# ESP32.net
KiCad netlist of a schematic drawn in Altium Designer
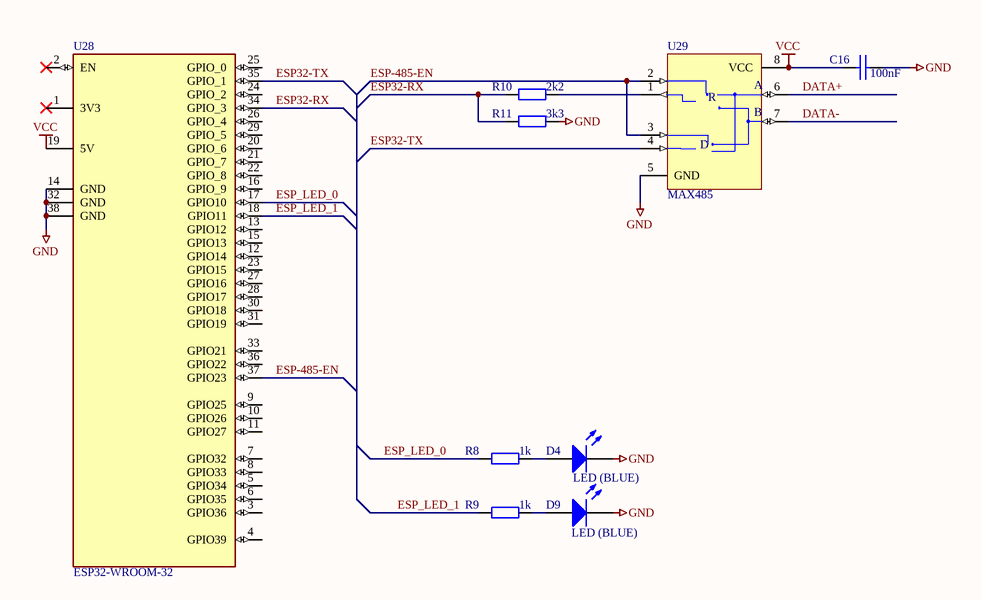
[diagram p0: ESP32.SchDoc]

(export (version "E")
  (design (tool "Eeschema 10.0.6"))
  (components
    (comp (ref "C16")
      (value "100nF")
      (footprint "CAPACITOR 0805")
      (description "CAPACITOR SMD 0603")
      (fields (field (name "MOUSER PART NO.") "81-GCM188R71C104KA7D") (field (name "MANUFACTURER") "Murata"))
      (libsource (lib "Mi-Call Schematic") (part "CAP"))
    )
    (comp (ref "D4")
      (value "LED (BLUE)")
      (footprint "LED(3D) 3MM VERTICAL (GREEN)")
      (description "3mm RED LED")
      (fields (field (name "MOUSER PART NO.") "604-WP132XIT") (field (name "FARNELL PART NO.") "1003393"))
      (libsource (lib "NASCO") (part "LED 3mm RED"))
    )
    (comp (ref "D9")
      (value "LED (BLUE)")
      (footprint "LED(3D) 3MM VERTICAL (GREEN)")
      (description "3mm RED LED")
      (fields (field (name "MOUSER PART NO.") "604-WP132XIT") (field (name "FARNELL PART NO.") "1003393"))
      (libsource (lib "NASCO") (part "LED 3mm RED"))
    )
    (comp (ref "R8")
      (value "1k")
      (footprint "RESISTOR 0805")
      (description "Resistor")
      (fields (field (name "PUBLISHER") "Altium Limited"))
      (libsource (lib "Miscellaneous Devices") (part "Res2"))
    )
    (comp (ref "R9")
      (value "1k")
      (footprint "RESISTOR 0805")
      (description "Resistor")
      (fields (field (name "PUBLISHER") "Altium Limited"))
      (libsource (lib "Miscellaneous Devices") (part "Res2"))
    )
    (comp (ref "R10")
      (value "2k2")
      (footprint "RESISTOR 0805")
      (description "Resistor")
      (fields (field (name "PUBLISHER") "Altium Limited"))
      (libsource (lib "Miscellaneous Devices") (part "Res2"))
    )
    (comp (ref "R11")
      (value "3k3")
      (footprint "RESISTOR 0805")
      (description "Resistor")
      (fields (field (name "PUBLISHER") "Altium Limited"))
      (libsource (lib "Miscellaneous Devices") (part "Res2"))
    )
    (comp (ref "U28")
      (value "ESP32-WROOM-32")
      (footprint "ESP-WROOM-32")
      (description "ESP-WROOM-32 38 PIN Develeopment Board PINOUT")
      (libsource (lib "XC Tail Light Driver") (part "ESP-WROOM-32 38 PIN Develeopment Board PINOUT"))
    )
    (comp (ref "U29")
      (value "MAX485")
      (footprint "SO-8")
      (description "MAX485 485/422 Transceiver")
      (fields (field (name "LCSC PART NUMBER") "C9945"))
      (libsource (lib "XC Tail Light Driver") (part "MAX487CPA"))
    )
  )
  (nets
    (net (code "1") (name "/DATA+") (class "Default")
      (node (ref "U29") (pin "6") (pinfunction "A_6") (pintype "bidirectional"))
    )
    (net (code "2") (name "/DATA-") (class "Default")
      (node (ref "U29") (pin "7") (pinfunction "B_7") (pintype "bidirectional"))
    )
    (net (code "3") (name "/ESP-485-EN") (class "Default")
      (node (ref "U28") (pin "37") (pinfunction "GPIO23_37") (pintype "bidirectional"))
      (node (ref "U29") (pin "2") (pinfunction "~{RE}_2") (pintype "input"))
      (node (ref "U29") (pin "3") (pinfunction "DE_3") (pintype "input"))
    )
    (net (code "4") (name "/ESP32-RX") (class "Default")
      (node (ref "R10") (pin "2") (pinfunction "2_2") (pintype "passive"))
      (node (ref "R11") (pin "2") (pinfunction "2_2") (pintype "passive"))
      (node (ref "U28") (pin "34") (pinfunction "GPIO_3_34") (pintype "bidirectional"))
    )
    (net (code "5") (name "/ESP32-TX") (class "Default")
      (node (ref "U28") (pin "35") (pinfunction "GPIO_1_35") (pintype "bidirectional"))
      (node (ref "U29") (pin "4") (pinfunction "DI_4") (pintype "input"))
    )
    (net (code "6") (name "/ESP_LED_0") (class "Default")
      (node (ref "R8") (pin "2") (pinfunction "2_2") (pintype "passive"))
      (node (ref "U28") (pin "17") (pinfunction "GPIO10_17") (pintype "bidirectional"))
    )
    (net (code "7") (name "/ESP_LED_1") (class "Default")
      (node (ref "R9") (pin "2") (pinfunction "2_2") (pintype "passive"))
      (node (ref "U28") (pin "18") (pinfunction "GPIO11_18") (pintype "bidirectional"))
    )
    (net (code "8") (name "GND") (class "Default")
      (node (ref "C16") (pin "2") (pinfunction "2_2") (pintype "passive"))
      (node (ref "D4") (pin "2") (pinfunction "K_2") (pintype "passive"))
      (node (ref "D9") (pin "2") (pinfunction "K_2") (pintype "passive"))
      (node (ref "R11") (pin "1") (pinfunction "1_1") (pintype "passive"))
      (node (ref "U28") (pin "14") (pinfunction "GND_14") (pintype "power_in"))
      (node (ref "U28") (pin "32") (pinfunction "GND_32") (pintype "power_in"))
      (node (ref "U28") (pin "38") (pinfunction "GND_38") (pintype "power_in"))
      (node (ref "U29") (pin "5") (pinfunction "GND_5") (pintype "power_in"))
    )
    (net (code "9") (name "Net-(D4-A)") (class "Default")
      (node (ref "D4") (pin "1") (pinfunction "A_1") (pintype "passive"))
      (node (ref "R8") (pin "1") (pinfunction "1_1") (pintype "passive"))
    )
    (net (code "10") (name "Net-(D9-A)") (class "Default")
      (node (ref "D9") (pin "1") (pinfunction "A_1") (pintype "passive"))
      (node (ref "R9") (pin "1") (pinfunction "1_1") (pintype "passive"))
    )
    (net (code "11") (name "Net-(U29-RO)") (class "Default")
      (node (ref "R10") (pin "1") (pinfunction "1_1") (pintype "passive"))
      (node (ref "U29") (pin "1") (pinfunction "RO_1") (pintype "output"))
    )
    (net (code "12") (name "VCC") (class "Default")
      (node (ref "C16") (pin "1") (pinfunction "1_1") (pintype "passive"))
      (node (ref "U28") (pin "19") (pinfunction "5V_19") (pintype "power_in"))
      (node (ref "U29") (pin "8") (pinfunction "VCC_8") (pintype "power_in"))
    )
    (net (code "13") (name "unconnected-(U28-3V3-Pad1)") (class "Default")
      (node (ref "U28") (pin "1") (pinfunction "3V3_1") (pintype "power_in+no_connect"))
    )
    (net (code "14") (name "unconnected-(U28-EN-Pad2)") (class "Default")
      (node (ref "U28") (pin "2") (pinfunction "EN_2") (pintype "bidirectional+no_connect"))
    )
    (net (code "15") (name "unconnected-(U28-GPIO12-Pad13)") (class "Default")
      (node (ref "U28") (pin "13") (pinfunction "GPIO12_13") (pintype "bidirectional"))
    )
    (net (code "16") (name "unconnected-(U28-GPIO13-Pad15)") (class "Default")
      (node (ref "U28") (pin "15") (pinfunction "GPIO13_15") (pintype "bidirectional"))
    )
    (net (code "17") (name "unconnected-(U28-GPIO14-Pad12)") (class "Default")
      (node (ref "U28") (pin "12") (pinfunction "GPIO14_12") (pintype "bidirectional"))
    )
    (net (code "18") (name "unconnected-(U28-GPIO15-Pad23)") (class "Default")
      (node (ref "U28") (pin "23") (pinfunction "GPIO15_23") (pintype "bidirectional"))
    )
    (net (code "19") (name "unconnected-(U28-GPIO16-Pad27)") (class "Default")
      (node (ref "U28") (pin "27") (pinfunction "GPIO16_27") (pintype "bidirectional"))
    )
    (net (code "20") (name "unconnected-(U28-GPIO17-Pad28)") (class "Default")
      (node (ref "U28") (pin "28") (pinfunction "GPIO17_28") (pintype "bidirectional"))
    )
    (net (code "21") (name "unconnected-(U28-GPIO18-Pad30)") (class "Default")
      (node (ref "U28") (pin "30") (pinfunction "GPIO18_30") (pintype "bidirectional"))
    )
    (net (code "22") (name "unconnected-(U28-GPIO19-Pad31)") (class "Default")
      (node (ref "U28") (pin "31") (pinfunction "GPIO19_31") (pintype "bidirectional"))
    )
    (net (code "23") (name "unconnected-(U28-GPIO21-Pad33)") (class "Default")
      (node (ref "U28") (pin "33") (pinfunction "GPIO21_33") (pintype "bidirectional"))
    )
    (net (code "24") (name "unconnected-(U28-GPIO22-Pad36)") (class "Default")
      (node (ref "U28") (pin "36") (pinfunction "GPIO22_36") (pintype "bidirectional"))
    )
    (net (code "25") (name "unconnected-(U28-GPIO25-Pad9)") (class "Default")
      (node (ref "U28") (pin "9") (pinfunction "GPIO25_9") (pintype "bidirectional"))
    )
    (net (code "26") (name "unconnected-(U28-GPIO26-Pad10)") (class "Default")
      (node (ref "U28") (pin "10") (pinfunction "GPIO26_10") (pintype "bidirectional"))
    )
    (net (code "27") (name "unconnected-(U28-GPIO27-Pad11)") (class "Default")
      (node (ref "U28") (pin "11") (pinfunction "GPIO27_11") (pintype "bidirectional"))
    )
    (net (code "28") (name "unconnected-(U28-GPIO32-Pad7)") (class "Default")
      (node (ref "U28") (pin "7") (pinfunction "GPIO32_7") (pintype "bidirectional"))
    )
    (net (code "29") (name "unconnected-(U28-GPIO33-Pad8)") (class "Default")
      (node (ref "U28") (pin "8") (pinfunction "GPIO33_8") (pintype "bidirectional"))
    )
    (net (code "30") (name "unconnected-(U28-GPIO34-Pad5)") (class "Default")
      (node (ref "U28") (pin "5") (pinfunction "GPIO34_5") (pintype "bidirectional"))
    )
    (net (code "31") (name "unconnected-(U28-GPIO35-Pad6)") (class "Default")
      (node (ref "U28") (pin "6") (pinfunction "GPIO35_6") (pintype "bidirectional"))
    )
    (net (code "32") (name "unconnected-(U28-GPIO36-Pad3)") (class "Default")
      (node (ref "U28") (pin "3") (pinfunction "GPIO36_3") (pintype "bidirectional"))
    )
    (net (code "33") (name "unconnected-(U28-GPIO39-Pad4)") (class "Default")
      (node (ref "U28") (pin "4") (pinfunction "GPIO39_4") (pintype "bidirectional"))
    )
    (net (code "34") (name "unconnected-(U28-GPIO_0-Pad25)") (class "Default")
      (node (ref "U28") (pin "25") (pinfunction "GPIO_0_25") (pintype "bidirectional"))
    )
    (net (code "35") (name "unconnected-(U28-GPIO_2-Pad24)") (class "Default")
      (node (ref "U28") (pin "24") (pinfunction "GPIO_2_24") (pintype "bidirectional"))
    )
    (net (code "36") (name "unconnected-(U28-GPIO_4-Pad26)") (class "Default")
      (node (ref "U28") (pin "26") (pinfunction "GPIO_4_26") (pintype "bidirectional"))
    )
    (net (code "37") (name "unconnected-(U28-GPIO_5-Pad29)") (class "Default")
      (node (ref "U28") (pin "29") (pinfunction "GPIO_5_29") (pintype "bidirectional"))
    )
    (net (code "38") (name "unconnected-(U28-GPIO_6-Pad20)") (class "Default")
      (node (ref "U28") (pin "20") (pinfunction "GPIO_6_20") (pintype "bidirectional"))
    )
    (net (code "39") (name "unconnected-(U28-GPIO_7-Pad21)") (class "Default")
      (node (ref "U28") (pin "21") (pinfunction "GPIO_7_21") (pintype "bidirectional"))
    )
    (net (code "40") (name "unconnected-(U28-GPIO_8-Pad22)") (class "Default")
      (node (ref "U28") (pin "22") (pinfunction "GPIO_8_22") (pintype "bidirectional"))
    )
    (net (code "41") (name "unconnected-(U28-GPIO_9-Pad16)") (class "Default")
      (node (ref "U28") (pin "16") (pinfunction "GPIO_9_16") (pintype "bidirectional"))
    )
  )
)
